# SCH___2022-10-18.net
KiCad netlist of a schematic drawn in EasyEDA
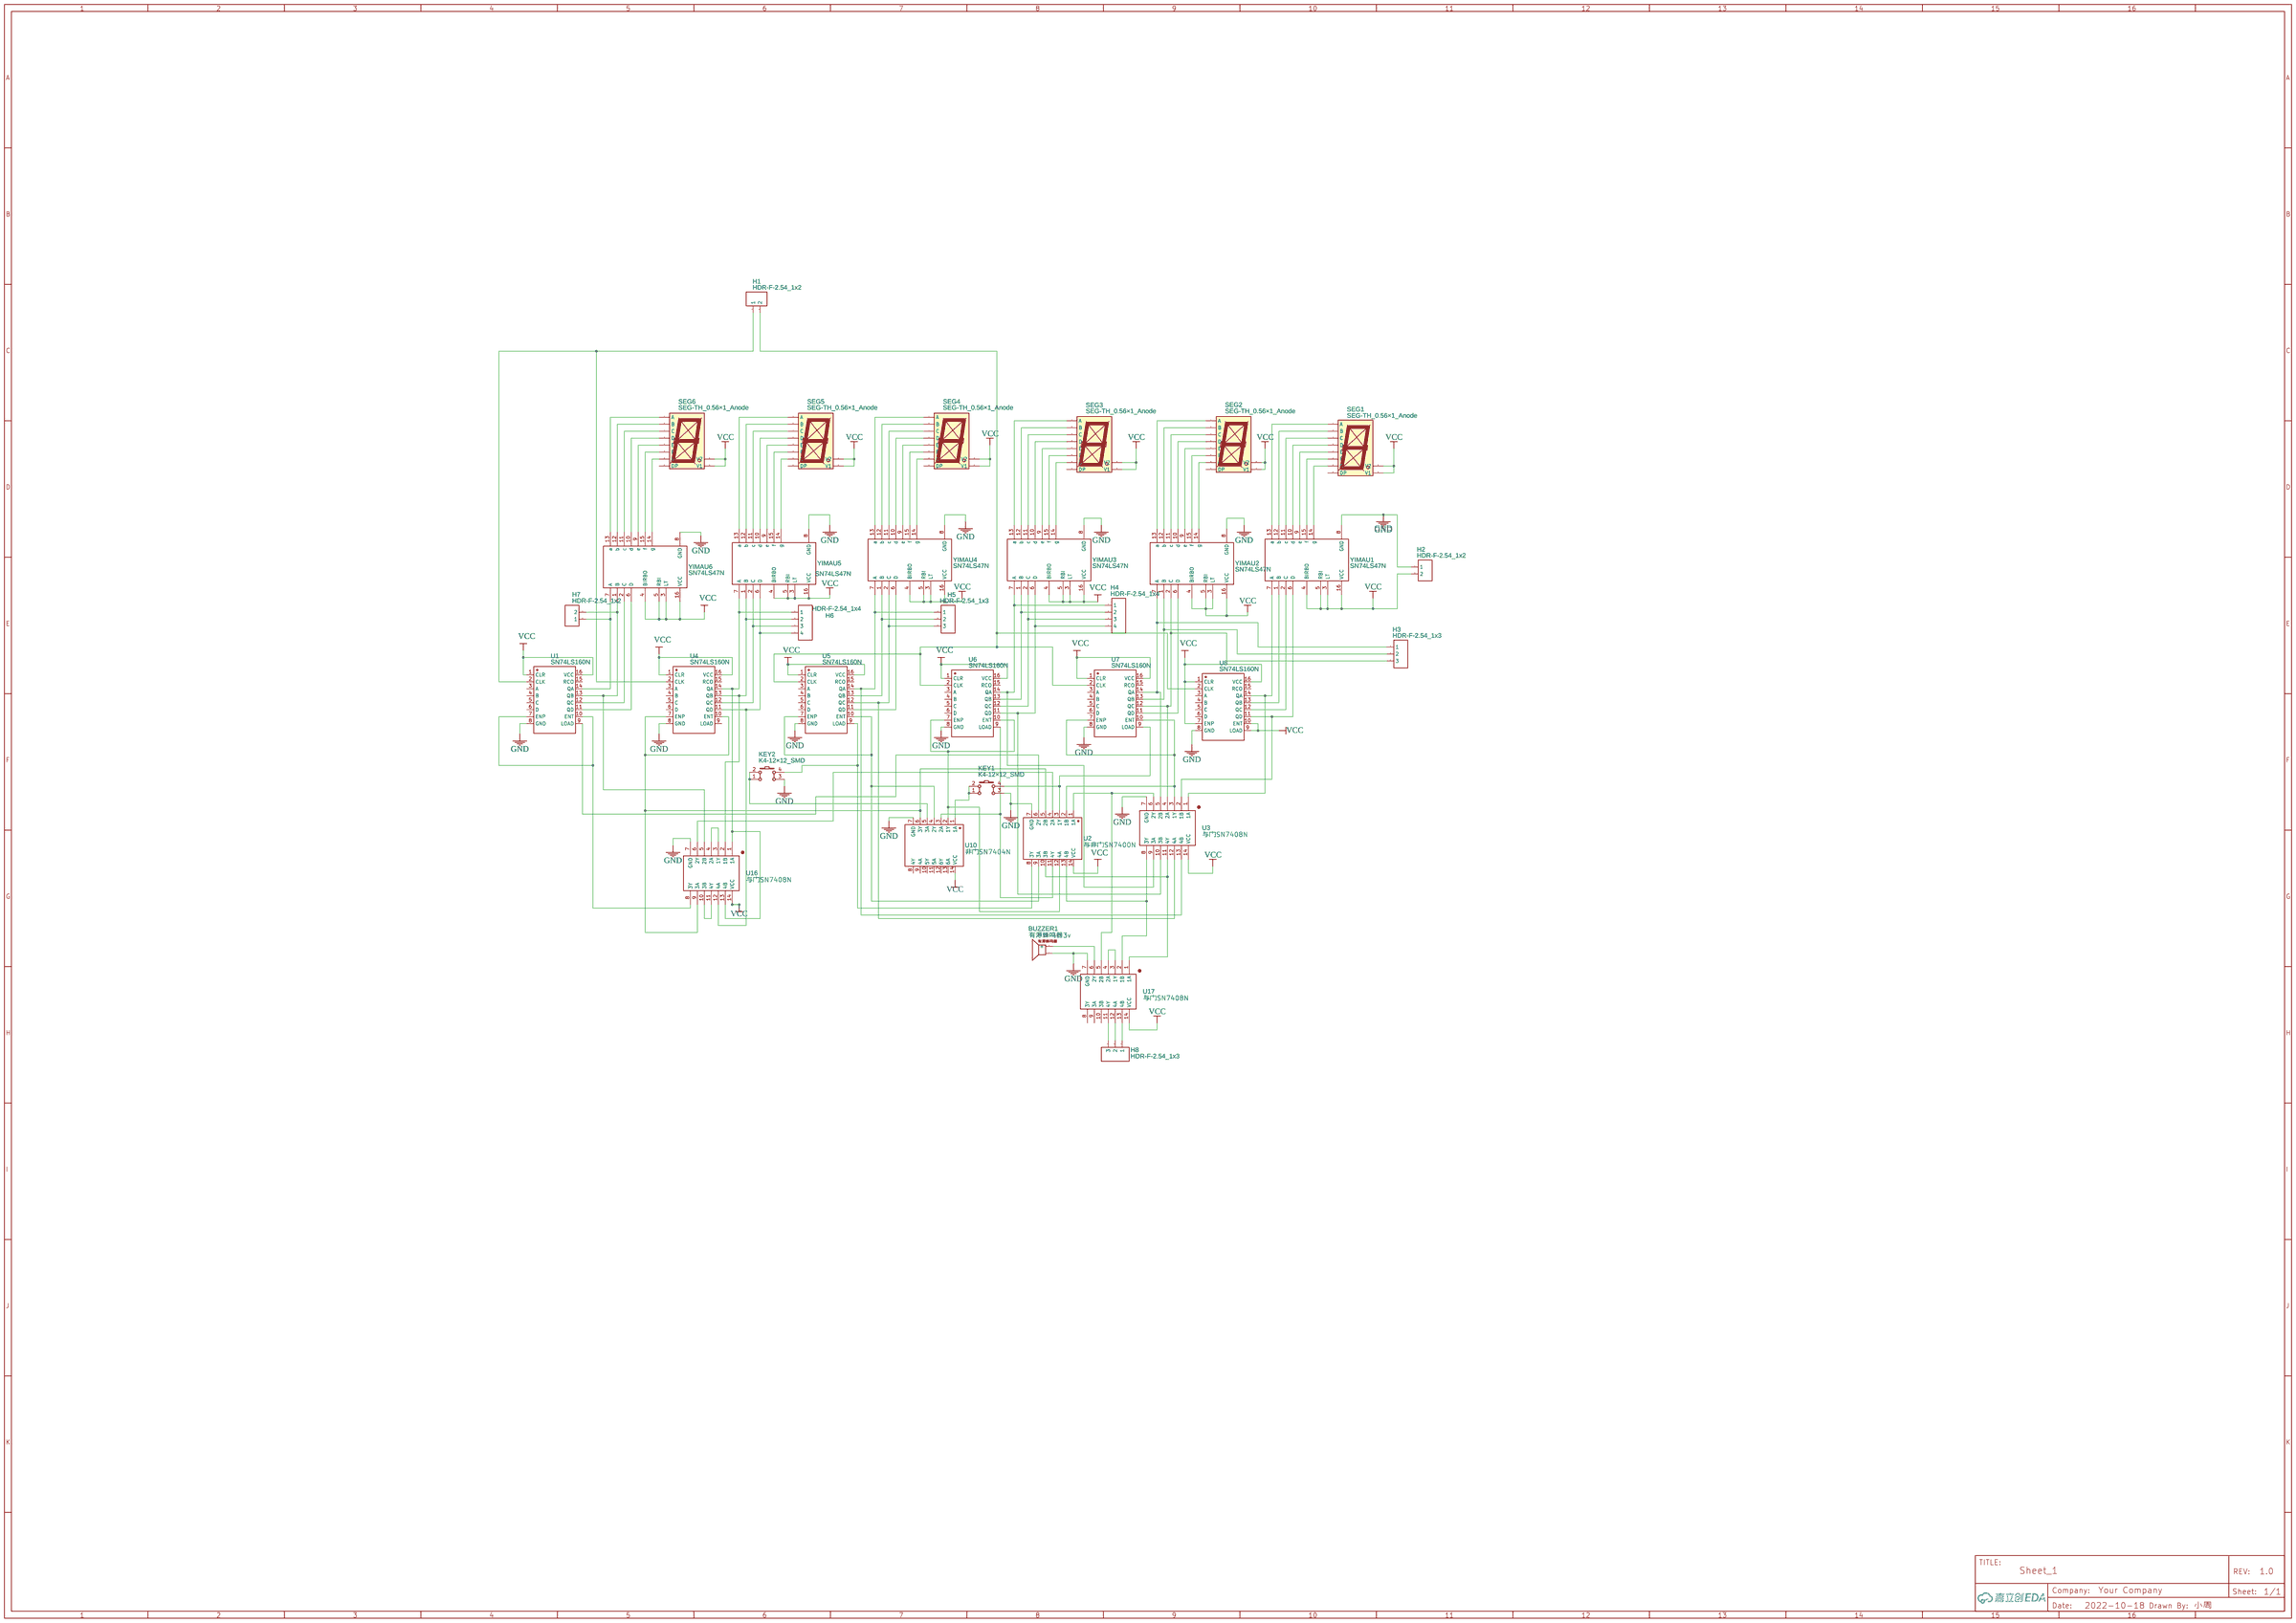
[diagram p0: schematic sheet]

(export (version "E")
  (design (tool "Eeschema 10.0.6"))
  (components
    (comp (ref "BUZZER1")
      (value "有源蜂鸣器3v")
      (fields (field (name "BOM_Manufacturer Part") "TMB12A12") (field (name "BOM_Supplier Part") "C96079"))
      (libsource (lib "") (part "有源蜂鸣器3v"))
    )
    (comp (ref "H1")
      (value "HDR-F-2.54_1x2")
      (fields (field (name "BOM_Supplier Part") "C49661"))
      (libsource (lib "") (part "HDR-F-2.54_1x2"))
    )
    (comp (ref "H2")
      (value "HDR-F-2.54_1x2")
      (fields (field (name "BOM_Supplier Part") "C49661"))
      (libsource (lib "") (part "HDR-F-2.54_1x2_2"))
    )
    (comp (ref "H3")
      (value "HDR-F-2.54_1x3")
      (fields (field (name "BOM_Supplier Part") "C146690"))
      (libsource (lib "") (part "HDR-F-2.54_1x3"))
    )
    (comp (ref "H4")
      (value "HDR-F-2.54_1x4")
      (fields (field (name "BOM_Supplier Part") "C225501"))
      (libsource (lib "") (part "HDR-F-2.54_1x4"))
    )
    (comp (ref "H5")
      (value "HDR-F-2.54_1x3")
      (fields (field (name "BOM_Supplier Part") "C146690"))
      (libsource (lib "") (part "HDR-F-2.54_1x3"))
    )
    (comp (ref "H6")
      (value "HDR-F-2.54_1x4")
      (fields (field (name "BOM_Supplier Part") "C225501"))
      (libsource (lib "") (part "HDR-F-2.54_1x4"))
    )
    (comp (ref "H7")
      (value "HDR-F-2.54_1x2")
      (fields (field (name "BOM_Supplier Part") "C49661"))
      (libsource (lib "") (part "HDR-F-2.54_1x2_1"))
    )
    (comp (ref "H8")
      (value "HDR-F-2.54_1x3")
      (fields (field (name "BOM_Supplier Part") "C146690"))
      (libsource (lib "") (part "HDR-F-2.54_1x3_1"))
    )
    (comp (ref "KEY1")
      (value "K4-12×12_SMD")
      (fields
        (field (name "BOM_Manufacturer Part") "K2-1103SP-E4SW-04")
        (field (name "BOM_Supplier Part") "C136697")
      )
      (libsource (lib "") (part "K4-12×12_SMD"))
    )
    (comp (ref "KEY2")
      (value "K4-12×12_SMD")
      (fields
        (field (name "BOM_Manufacturer Part") "K2-1103SP-E4SW-04")
        (field (name "BOM_Supplier Part") "C136697")
      )
      (libsource (lib "") (part "K4-12×12_SMD"))
    )
    (comp (ref "SEG1")
      (value "SEG-TH_0.56×1_Anode")
      (fields (field (name "BOM_Supplier Part") "C8092"))
      (libsource (lib "") (part "SEG-TH_0.56×1_Anode"))
    )
    (comp (ref "SEG2")
      (value "SEG-TH_0.56×1_Anode")
      (fields (field (name "BOM_Supplier Part") "C8092"))
      (libsource (lib "") (part "SEG-TH_0.56×1_Anode"))
    )
    (comp (ref "SEG3")
      (value "SEG-TH_0.56×1_Anode")
      (fields (field (name "BOM_Supplier Part") "C8092"))
      (libsource (lib "") (part "SEG-TH_0.56×1_Anode"))
    )
    (comp (ref "SEG4")
      (value "SEG-TH_0.56×1_Anode")
      (fields (field (name "BOM_Supplier Part") "C8092"))
      (libsource (lib "") (part "SEG-TH_0.56×1_Anode"))
    )
    (comp (ref "SEG5")
      (value "SEG-TH_0.56×1_Anode")
      (fields (field (name "BOM_Supplier Part") "C8092"))
      (libsource (lib "") (part "SEG-TH_0.56×1_Anode"))
    )
    (comp (ref "SEG6")
      (value "SEG-TH_0.56×1_Anode")
      (fields (field (name "BOM_Supplier Part") "C8092"))
      (libsource (lib "") (part "SEG-TH_0.56×1_Anode"))
    )
    (comp (ref "U1")
      (value "SN74LS160N")
      (fields
        (field (name "BOM_Manufacturer Part") "CC0805JRNPO9BN821")
        (field (name "BOM_Supplier Part") "C113834")
      )
      (libsource (lib "") (part "SN74LS160N"))
    )
    (comp (ref "U2") (value "与非门SN7400N") (libsource (lib "") (part "SN7400N")))
    (comp (ref "U3") (value "与门SN7408N") (libsource (lib "") (part "SN7408N")))
    (comp (ref "U4")
      (value "SN74LS160N")
      (fields
        (field (name "BOM_Manufacturer Part") "CC0805JRNPO9BN821")
        (field (name "BOM_Supplier Part") "C113834")
      )
      (libsource (lib "") (part "SN74LS160N"))
    )
    (comp (ref "U5")
      (value "SN74LS160N")
      (fields
        (field (name "BOM_Manufacturer Part") "CC0805JRNPO9BN821")
        (field (name "BOM_Supplier Part") "C113834")
      )
      (libsource (lib "") (part "SN74LS160N"))
    )
    (comp (ref "U6")
      (value "SN74LS160N")
      (fields
        (field (name "BOM_Manufacturer Part") "CC0805JRNPO9BN821")
        (field (name "BOM_Supplier Part") "C113834")
      )
      (libsource (lib "") (part "SN74LS160N"))
    )
    (comp (ref "U7")
      (value "SN74LS160N")
      (fields
        (field (name "BOM_Manufacturer Part") "CC0805JRNPO9BN821")
        (field (name "BOM_Supplier Part") "C113834")
      )
      (libsource (lib "") (part "SN74LS160N"))
    )
    (comp (ref "U8")
      (value "SN74LS160N")
      (fields
        (field (name "BOM_Manufacturer Part") "CC0805JRNPO9BN821")
        (field (name "BOM_Supplier Part") "C113834")
      )
      (libsource (lib "") (part "SN74LS160N"))
    )
    (comp (ref "U10") (value "非门SN7404N") (libsource (lib "") (part "SN7404N")))
    (comp (ref "U16") (value "与门SN7408N") (libsource (lib "") (part "SN7408N")))
    (comp (ref "U17") (value "与门SN7408N") (libsource (lib "") (part "SN7408N")))
    (comp (ref "YIMAU1")
      (value "SN74LS47N")
      (fields (field (name "BOM_Supplier Part") "C129379"))
      (libsource (lib "") (part "Unknown_1870_-1520"))
    )
    (comp (ref "YIMAU2")
      (value "SN74LS47N")
      (fields (field (name "BOM_Supplier Part") "C129379"))
      (libsource (lib "") (part "Unknown_1705_-1515"))
    )
    (comp (ref "YIMAU3")
      (value "SN74LS47N")
      (fields (field (name "BOM_Supplier Part") "C129379"))
      (libsource (lib "") (part "Unknown_1500_-1520"))
    )
    (comp (ref "YIMAU4")
      (value "SN74LS47N")
      (fields (field (name "BOM_Supplier Part") "C129379"))
      (libsource (lib "") (part "Unknown_1300_-1520"))
    )
    (comp (ref "YIMAU5")
      (value "SN74LS47N")
      (fields (field (name "BOM_Supplier Part") "C129379"))
      (libsource (lib "") (part "Unknown_1105_-1515"))
    )
    (comp (ref "YIMAU6")
      (value "SN74LS47N")
      (fields (field (name "BOM_Supplier Part") "C129379"))
      (libsource (lib "") (part "Unknown_920_-1510"))
    )
  )
  (nets
    (net (code "1") (name "GND") (class "Default")
      (node (ref "BUZZER1") (pin "-") (pinfunction "-_-") (pintype "unspecified"))
      (node (ref "H2") (pin "1") (pinfunction "1_1") (pintype "input"))
      (node (ref "KEY1") (pin "3") (pinfunction "3_3") (pintype "unspecified"))
      (node (ref "KEY2") (pin "3") (pinfunction "3_3") (pintype "unspecified"))
      (node (ref "U1") (pin "8") (pinfunction "GND_8") (pintype "unspecified"))
      (node (ref "U10") (pin "7") (pinfunction "GND_7") (pintype "unspecified"))
      (node (ref "U16") (pin "7") (pinfunction "GND_7") (pintype "unspecified"))
      (node (ref "U17") (pin "7") (pinfunction "GND_7") (pintype "unspecified"))
      (node (ref "U2") (pin "7") (pinfunction "GND_7") (pintype "unspecified"))
      (node (ref "U3") (pin "7") (pinfunction "GND_7") (pintype "unspecified"))
      (node (ref "U4") (pin "8") (pinfunction "GND_8") (pintype "unspecified"))
      (node (ref "U5") (pin "8") (pinfunction "GND_8") (pintype "unspecified"))
      (node (ref "U6") (pin "8") (pinfunction "GND_8") (pintype "unspecified"))
      (node (ref "U7") (pin "8") (pinfunction "GND_8") (pintype "unspecified"))
      (node (ref "U8") (pin "8") (pinfunction "GND_8") (pintype "unspecified"))
      (node (ref "YIMAU1") (pin "8") (pinfunction "GND_8") (pintype "passive"))
      (node (ref "YIMAU2") (pin "8") (pinfunction "GND_8") (pintype "passive"))
      (node (ref "YIMAU3") (pin "8") (pinfunction "GND_8") (pintype "passive"))
      (node (ref "YIMAU4") (pin "8") (pinfunction "GND_8") (pintype "passive"))
      (node (ref "YIMAU5") (pin "8") (pinfunction "GND_8") (pintype "passive"))
      (node (ref "YIMAU6") (pin "8") (pinfunction "GND_8") (pintype "passive"))
    )
    (net (code "2") (name "Net-(SEG1-A)") (class "Default")
      (node (ref "SEG1") (pin "7") (pinfunction "A_7") (pintype "unspecified"))
      (node (ref "YIMAU1") (pin "13") (pinfunction "a_13") (pintype "unspecified"))
    )
    (net (code "3") (name "Net-(SEG1-B)") (class "Default")
      (node (ref "SEG1") (pin "6") (pinfunction "B_6") (pintype "unspecified"))
      (node (ref "YIMAU1") (pin "12") (pinfunction "b_12") (pintype "unspecified"))
    )
    (net (code "4") (name "Net-(SEG1-C)") (class "Default")
      (node (ref "SEG1") (pin "4") (pinfunction "C_4") (pintype "unspecified"))
      (node (ref "YIMAU1") (pin "11") (pinfunction "c_11") (pintype "unspecified"))
    )
    (net (code "5") (name "Net-(SEG1-D)") (class "Default")
      (node (ref "SEG1") (pin "2") (pinfunction "D_2") (pintype "unspecified"))
      (node (ref "YIMAU1") (pin "10") (pinfunction "d_10") (pintype "unspecified"))
    )
    (net (code "6") (name "Net-(SEG1-E)") (class "Default")
      (node (ref "SEG1") (pin "1") (pinfunction "E_1") (pintype "unspecified"))
      (node (ref "YIMAU1") (pin "9") (pinfunction "e_9") (pintype "unspecified"))
    )
    (net (code "7") (name "Net-(SEG1-F)") (class "Default")
      (node (ref "SEG1") (pin "9") (pinfunction "F_9") (pintype "unspecified"))
      (node (ref "YIMAU1") (pin "15") (pinfunction "f_15") (pintype "unspecified"))
    )
    (net (code "8") (name "Net-(SEG1-G)") (class "Default")
      (node (ref "SEG1") (pin "10") (pinfunction "G_10") (pintype "unspecified"))
      (node (ref "YIMAU1") (pin "14") (pinfunction "g_14") (pintype "unspecified"))
    )
    (net (code "9") (name "Net-(SEG2-A)") (class "Default")
      (node (ref "SEG2") (pin "7") (pinfunction "A_7") (pintype "unspecified"))
      (node (ref "YIMAU2") (pin "13") (pinfunction "a_13") (pintype "unspecified"))
    )
    (net (code "10") (name "Net-(SEG2-B)") (class "Default")
      (node (ref "SEG2") (pin "6") (pinfunction "B_6") (pintype "unspecified"))
      (node (ref "YIMAU2") (pin "12") (pinfunction "b_12") (pintype "unspecified"))
    )
    (net (code "11") (name "Net-(SEG2-C)") (class "Default")
      (node (ref "SEG2") (pin "4") (pinfunction "C_4") (pintype "unspecified"))
      (node (ref "YIMAU2") (pin "11") (pinfunction "c_11") (pintype "unspecified"))
    )
    (net (code "12") (name "Net-(SEG2-D)") (class "Default")
      (node (ref "SEG2") (pin "2") (pinfunction "D_2") (pintype "unspecified"))
      (node (ref "YIMAU2") (pin "10") (pinfunction "d_10") (pintype "unspecified"))
    )
    (net (code "13") (name "Net-(SEG2-E)") (class "Default")
      (node (ref "SEG2") (pin "1") (pinfunction "E_1") (pintype "unspecified"))
      (node (ref "YIMAU2") (pin "9") (pinfunction "e_9") (pintype "unspecified"))
    )
    (net (code "14") (name "Net-(SEG2-F)") (class "Default")
      (node (ref "SEG2") (pin "9") (pinfunction "F_9") (pintype "unspecified"))
      (node (ref "YIMAU2") (pin "15") (pinfunction "f_15") (pintype "unspecified"))
    )
    (net (code "15") (name "Net-(SEG2-G)") (class "Default")
      (node (ref "SEG2") (pin "10") (pinfunction "G_10") (pintype "unspecified"))
      (node (ref "YIMAU2") (pin "14") (pinfunction "g_14") (pintype "unspecified"))
    )
    (net (code "16") (name "Net-(SEG3-A)") (class "Default")
      (node (ref "SEG3") (pin "7") (pinfunction "A_7") (pintype "unspecified"))
      (node (ref "YIMAU3") (pin "13") (pinfunction "a_13") (pintype "unspecified"))
    )
    (net (code "17") (name "Net-(SEG3-B)") (class "Default")
      (node (ref "SEG3") (pin "6") (pinfunction "B_6") (pintype "unspecified"))
      (node (ref "YIMAU3") (pin "12") (pinfunction "b_12") (pintype "unspecified"))
    )
    (net (code "18") (name "Net-(SEG3-C)") (class "Default")
      (node (ref "SEG3") (pin "4") (pinfunction "C_4") (pintype "unspecified"))
      (node (ref "YIMAU3") (pin "11") (pinfunction "c_11") (pintype "unspecified"))
    )
    (net (code "19") (name "Net-(SEG3-D)") (class "Default")
      (node (ref "SEG3") (pin "2") (pinfunction "D_2") (pintype "unspecified"))
      (node (ref "YIMAU3") (pin "10") (pinfunction "d_10") (pintype "unspecified"))
    )
    (net (code "20") (name "Net-(SEG3-E)") (class "Default")
      (node (ref "SEG3") (pin "1") (pinfunction "E_1") (pintype "unspecified"))
      (node (ref "YIMAU3") (pin "9") (pinfunction "e_9") (pintype "unspecified"))
    )
    (net (code "21") (name "Net-(SEG3-F)") (class "Default")
      (node (ref "SEG3") (pin "9") (pinfunction "F_9") (pintype "unspecified"))
      (node (ref "YIMAU3") (pin "15") (pinfunction "f_15") (pintype "unspecified"))
    )
    (net (code "22") (name "Net-(SEG3-G)") (class "Default")
      (node (ref "SEG3") (pin "10") (pinfunction "G_10") (pintype "unspecified"))
      (node (ref "YIMAU3") (pin "14") (pinfunction "g_14") (pintype "unspecified"))
    )
    (net (code "23") (name "Net-(SEG4-A)") (class "Default")
      (node (ref "SEG4") (pin "7") (pinfunction "A_7") (pintype "unspecified"))
      (node (ref "YIMAU4") (pin "13") (pinfunction "a_13") (pintype "unspecified"))
    )
    (net (code "24") (name "Net-(SEG4-B)") (class "Default")
      (node (ref "SEG4") (pin "6") (pinfunction "B_6") (pintype "unspecified"))
      (node (ref "YIMAU4") (pin "12") (pinfunction "b_12") (pintype "unspecified"))
    )
    (net (code "25") (name "Net-(SEG4-C)") (class "Default")
      (node (ref "SEG4") (pin "4") (pinfunction "C_4") (pintype "unspecified"))
      (node (ref "YIMAU4") (pin "11") (pinfunction "c_11") (pintype "unspecified"))
    )
    (net (code "26") (name "Net-(SEG4-D)") (class "Default")
      (node (ref "SEG4") (pin "2") (pinfunction "D_2") (pintype "unspecified"))
      (node (ref "YIMAU4") (pin "10") (pinfunction "d_10") (pintype "unspecified"))
    )
    (net (code "27") (name "Net-(SEG4-E)") (class "Default")
      (node (ref "SEG4") (pin "1") (pinfunction "E_1") (pintype "unspecified"))
      (node (ref "YIMAU4") (pin "9") (pinfunction "e_9") (pintype "unspecified"))
    )
    (net (code "28") (name "Net-(SEG4-F)") (class "Default")
      (node (ref "SEG4") (pin "9") (pinfunction "F_9") (pintype "unspecified"))
      (node (ref "YIMAU4") (pin "15") (pinfunction "f_15") (pintype "unspecified"))
    )
    (net (code "29") (name "Net-(SEG4-G)") (class "Default")
      (node (ref "SEG4") (pin "10") (pinfunction "G_10") (pintype "unspecified"))
      (node (ref "YIMAU4") (pin "14") (pinfunction "g_14") (pintype "unspecified"))
    )
    (net (code "30") (name "Net-(SEG5-A)") (class "Default")
      (node (ref "SEG5") (pin "7") (pinfunction "A_7") (pintype "unspecified"))
      (node (ref "YIMAU5") (pin "13") (pinfunction "a_13") (pintype "unspecified"))
    )
    (net (code "31") (name "Net-(SEG5-B)") (class "Default")
      (node (ref "SEG5") (pin "6") (pinfunction "B_6") (pintype "unspecified"))
      (node (ref "YIMAU5") (pin "12") (pinfunction "b_12") (pintype "unspecified"))
    )
    (net (code "32") (name "Net-(SEG5-C)") (class "Default")
      (node (ref "SEG5") (pin "4") (pinfunction "C_4") (pintype "unspecified"))
      (node (ref "YIMAU5") (pin "11") (pinfunction "c_11") (pintype "unspecified"))
    )
    (net (code "33") (name "Net-(SEG5-D)") (class "Default")
      (node (ref "SEG5") (pin "2") (pinfunction "D_2") (pintype "unspecified"))
      (node (ref "YIMAU5") (pin "10") (pinfunction "d_10") (pintype "unspecified"))
    )
    (net (code "34") (name "Net-(SEG5-E)") (class "Default")
      (node (ref "SEG5") (pin "1") (pinfunction "E_1") (pintype "unspecified"))
      (node (ref "YIMAU5") (pin "9") (pinfunction "e_9") (pintype "unspecified"))
    )
    (net (code "35") (name "Net-(SEG5-F)") (class "Default")
      (node (ref "SEG5") (pin "9") (pinfunction "F_9") (pintype "unspecified"))
      (node (ref "YIMAU5") (pin "15") (pinfunction "f_15") (pintype "unspecified"))
    )
    (net (code "36") (name "Net-(SEG5-G)") (class "Default")
      (node (ref "SEG5") (pin "10") (pinfunction "G_10") (pintype "unspecified"))
      (node (ref "YIMAU5") (pin "14") (pinfunction "g_14") (pintype "unspecified"))
    )
    (net (code "37") (name "Net-(SEG6-A)") (class "Default")
      (node (ref "SEG6") (pin "7") (pinfunction "A_7") (pintype "unspecified"))
      (node (ref "YIMAU6") (pin "13") (pinfunction "a_13") (pintype "unspecified"))
    )
    (net (code "38") (name "Net-(SEG6-B)") (class "Default")
      (node (ref "SEG6") (pin "6") (pinfunction "B_6") (pintype "unspecified"))
      (node (ref "YIMAU6") (pin "12") (pinfunction "b_12") (pintype "unspecified"))
    )
    (net (code "39") (name "Net-(SEG6-C)") (class "Default")
      (node (ref "SEG6") (pin "4") (pinfunction "C_4") (pintype "unspecified"))
      (node (ref "YIMAU6") (pin "11") (pinfunction "c_11") (pintype "unspecified"))
    )
    (net (code "40") (name "Net-(SEG6-D)") (class "Default")
      (node (ref "SEG6") (pin "2") (pinfunction "D_2") (pintype "unspecified"))
      (node (ref "YIMAU6") (pin "10") (pinfunction "d_10") (pintype "unspecified"))
    )
    (net (code "41") (name "Net-(SEG6-E)") (class "Default")
      (node (ref "SEG6") (pin "1") (pinfunction "E_1") (pintype "unspecified"))
      (node (ref "YIMAU6") (pin "9") (pinfunction "e_9") (pintype "unspecified"))
    )
    (net (code "42") (name "Net-(SEG6-F)") (class "Default")
      (node (ref "SEG6") (pin "9") (pinfunction "F_9") (pintype "unspecified"))
      (node (ref "YIMAU6") (pin "15") (pinfunction "f_15") (pintype "unspecified"))
    )
    (net (code "43") (name "Net-(SEG6-G)") (class "Default")
      (node (ref "SEG6") (pin "10") (pinfunction "G_10") (pintype "unspecified"))
      (node (ref "YIMAU6") (pin "14") (pinfunction "g_14") (pintype "unspecified"))
    )
    (net (code "44") (name "Net-(U1-CLK)") (class "Default")
      (node (ref "H1") (pin "1") (pinfunction "1_1") (pintype "input"))
      (node (ref "U1") (pin "2") (pinfunction "CLK_2") (pintype "unspecified"))
      (node (ref "U4") (pin "2") (pinfunction "CLK_2") (pintype "unspecified"))
    )
    (net (code "45") (name "Net-(U1-ENP)") (class "Default")
      (node (ref "U1") (pin "10") (pinfunction "ENT_10") (pintype "unspecified"))
      (node (ref "U1") (pin "7") (pinfunction "ENP_7") (pintype "unspecified"))
      (node (ref "U16") (pin "8") (pinfunction "3Y_8") (pintype "unspecified"))
    )
    (net (code "46") (name "Net-(U1-LOAD)") (class "Default")
      (node (ref "U1") (pin "9") (pinfunction "LOAD_9") (pintype "unspecified"))
      (node (ref "U2") (pin "6") (pinfunction "2Y_6") (pintype "unspecified"))
    )
    (net (code "47") (name "Net-(U1-QA)") (class "Default")
      (node (ref "H7") (pin "1") (pinfunction "1_1") (pintype "input"))
      (node (ref "U1") (pin "14") (pinfunction "QA_14") (pintype "unspecified"))
      (node (ref "YIMAU6") (pin "7") (pinfunction "A_7") (pintype "unspecified"))
    )
    (net (code "48") (name "Net-(U1-QB)") (class "Default")
      (node (ref "H7") (pin "2") (pinfunction "2_2") (pintype "input"))
      (node (ref "U1") (pin "13") (pinfunction "QB_13") (pintype "unspecified"))
      (node (ref "U16") (pin "5") (pinfunction "2B_5") (pintype "unspecified"))
      (node (ref "YIMAU6") (pin "1") (pinfunction "B_1") (pintype "unspecified"))
    )
    (net (code "49") (name "Net-(U1-QC)") (class "Default")
      (node (ref "U1") (pin "12") (pinfunction "QC_12") (pintype "unspecified"))
      (node (ref "YIMAU6") (pin "2") (pinfunction "C_2") (pintype "unspecified"))
    )
    (net (code "50") (name "Net-(U1-QD)") (class "Default")
      (node (ref "U1") (pin "11") (pinfunction "QD_11") (pintype "unspecified"))
      (node (ref "YIMAU6") (pin "6") (pinfunction "D_6") (pintype "unspecified"))
    )
    (net (code "51") (name "Net-(U2-1B)") (class "Default")
      (node (ref "U2") (pin "2") (pinfunction "1B_2") (pintype "unspecified"))
      (node (ref "U3") (pin "3") (pinfunction "1Y_3") (pintype "unspecified"))
      (node (ref "U7") (pin "10") (pinfunction "ENT_10") (pintype "unspecified"))
      (node (ref "U7") (pin "7") (pinfunction "ENP_7") (pintype "unspecified"))
    )
    (net (code "52") (name "Net-(U2-1Y)") (class "Default")
      (node (ref "KEY1") (pin "4") (pinfunction "4_4") (pintype "unspecified"))
      (node (ref "U2") (pin "3") (pinfunction "1Y_3") (pintype "unspecified"))
      (node (ref "U7") (pin "9") (pinfunction "LOAD_9") (pintype "unspecified"))
    )
    (net (code "53") (name "Net-(U2-3Y)") (class "Default")
      (node (ref "KEY2") (pin "4") (pinfunction "4_4") (pintype "unspecified"))
      (node (ref "U2") (pin "8") (pinfunction "3Y_8") (pintype "unspecified"))
      (node (ref "U5") (pin "9") (pinfunction "LOAD_9") (pintype "unspecified"))
    )
    (net (code "54") (name "Net-(U3-1A)") (class "Default")
      (node (ref "U3") (pin "1") (pinfunction "1A_1") (pintype "unspecified"))
      (node (ref "U8") (pin "14") (pinfunction "QA_14") (pintype "unspecified"))
      (node (ref "YIMAU1") (pin "7") (pinfunction "A_7") (pintype "unspecified"))
    )
    (net (code "55") (name "Net-(U3-1B)") (class "Default")
      (node (ref "U3") (pin "2") (pinfunction "1B_2") (pintype "unspecified"))
      (node (ref "U8") (pin "11") (pinfunction "QD_11") (pintype "unspecified"))
      (node (ref "YIMAU1") (pin "6") (pinfunction "D_6") (pintype "unspecified"))
    )
    (net (code "56") (name "Net-(U3-2A)") (class "Default")
      (node (ref "H3") (pin "3") (pinfunction "3_3") (pintype "input"))
      (node (ref "U3") (pin "4") (pinfunction "2A_4") (pintype "unspecified"))
      (node (ref "U7") (pin "12") (pinfunction "QC_12") (pintype "unspecified"))
      (node (ref "YIMAU2") (pin "2") (pinfunction "C_2") (pintype "unspecified"))
    )
    (net (code "57") (name "Net-(U3-2B)") (class "Default")
      (node (ref "H3") (pin "1") (pinfunction "1_1") (pintype "input"))
      (node (ref "U3") (pin "5") (pinfunction "2B_5") (pintype "unspecified"))
      (node (ref "U7") (pin "14") (pinfunction "QA_14") (pintype "unspecified"))
      (node (ref "YIMAU2") (pin "7") (pinfunction "A_7") (pintype "unspecified"))
    )
    (net (code "58") (name "Net-(U3-3A)") (class "Default")
      (node (ref "H4") (pin "1") (pinfunction "1_1") (pintype "unspecified"))
      (node (ref "U3") (pin "9") (pinfunction "3A_9") (pintype "unspecified"))
      (node (ref "U6") (pin "14") (pinfunction "QA_14") (pintype "unspecified"))
      (node (ref "YIMAU3") (pin "7") (pinfunction "A_7") (pintype "unspecified"))
    )
    (net (code "59") (name "Net-(U3-3B)") (class "Default")
      (node (ref "H4") (pin "4") (pinfunction "4_4") (pintype "unspecified"))
      (node (ref "U3") (pin "10") (pinfunction "3B_10") (pintype "unspecified"))
      (node (ref "U6") (pin "11") (pinfunction "QD_11") (pintype "unspecified"))
      (node (ref "YIMAU3") (pin "6") (pinfunction "D_6") (pintype "unspecified"))
    )
    (net (code "60") (name "Net-(U3-4A)") (class "Default")
      (node (ref "H5") (pin "3") (pinfunction "3_3") (pintype "input"))
      (node (ref "U3") (pin "12") (pinfunction "4A_12") (pintype "unspecified"))
      (node (ref "U5") (pin "12") (pinfunction "QC_12") (pintype "unspecified"))
      (node (ref "YIMAU4") (pin "2") (pinfunction "C_2") (pintype "unspecified"))
    )
    (net (code "61") (name "Net-(U3-4B)") (class "Default")
      (node (ref "H5") (pin "1") (pinfunction "1_1") (pintype "input"))
      (node (ref "U3") (pin "13") (pinfunction "4B_13") (pintype "unspecified"))
      (node (ref "U5") (pin "14") (pinfunction "QA_14") (pintype "unspecified"))
      (node (ref "YIMAU4") (pin "7") (pinfunction "A_7") (pintype "unspecified"))
    )
    (net (code "62") (name "Net-(U4-QC)") (class "Default")
      (node (ref "H6") (pin "3") (pinfunction "3_3") (pintype "unspecified"))
      (node (ref "U4") (pin "12") (pinfunction "QC_12") (pintype "unspecified"))
      (node (ref "YIMAU5") (pin "2") (pinfunction "C_2") (pintype "unspecified"))
    )
    (net (code "63") (name "Net-(U5-CLK)") (class "Default")
      (node (ref "H1") (pin "2") (pinfunction "2_2") (pintype "input"))
      (node (ref "U5") (pin "2") (pinfunction "CLK_2") (pintype "unspecified"))
      (node (ref "U6") (pin "2") (pinfunction "CLK_2") (pintype "unspecified"))
      (node (ref "U7") (pin "2") (pinfunction "CLK_2") (pintype "unspecified"))
      (node (ref "U8") (pin "2") (pinfunction "CLK_2") (pintype "unspecified"))
    )
    (net (code "64") (name "Net-(U5-QB)") (class "Default")
      (node (ref "H5") (pin "2") (pinfunction "2_2") (pintype "input"))
      (node (ref "U5") (pin "13") (pinfunction "QB_13") (pintype "unspecified"))
      (node (ref "YIMAU4") (pin "1") (pinfunction "B_1") (pintype "unspecified"))
    )
    (net (code "65") (name "Net-(U5-QD)") (class "Default")
      (node (ref "U5") (pin "11") (pinfunction "QD_11") (pintype "unspecified"))
      (node (ref "YIMAU4") (pin "6") (pinfunction "D_6") (pintype "unspecified"))
    )
    (net (code "66") (name "Net-(U6-QB)") (class "Default")
      (node (ref "H4") (pin "2") (pinfunction "2_2") (pintype "unspecified"))
      (node (ref "U6") (pin "13") (pinfunction "QB_13") (pintype "unspecified"))
      (node (ref "YIMAU3") (pin "1") (pinfunction "B_1") (pintype "unspecified"))
    )
    (net (code "67") (name "Net-(U6-QC)") (class "Default")
      (node (ref "H4") (pin "3") (pinfunction "3_3") (pintype "unspecified"))
      (node (ref "U6") (pin "12") (pinfunction "QC_12") (pintype "unspecified"))
      (node (ref "YIMAU3") (pin "2") (pinfunction "C_2") (pintype "unspecified"))
    )
    (net (code "68") (name "Net-(U7-QB)") (class "Default")
      (node (ref "H3") (pin "2") (pinfunction "2_2") (pintype "input"))
      (node (ref "U7") (pin "13") (pinfunction "QB_13") (pintype "unspecified"))
      (node (ref "YIMAU2") (pin "1") (pinfunction "B_1") (pintype "unspecified"))
    )
    (net (code "69") (name "Net-(U7-QD)") (class "Default")
      (node (ref "U7") (pin "11") (pinfunction "QD_11") (pintype "unspecified"))
      (node (ref "YIMAU2") (pin "6") (pinfunction "D_6") (pintype "unspecified"))
    )
    (net (code "70") (name "Net-(U8-QB)") (class "Default")
      (node (ref "U8") (pin "13") (pinfunction "QB_13") (pintype "unspecified"))
      (node (ref "YIMAU1") (pin "1") (pinfunction "B_1") (pintype "unspecified"))
    )
    (net (code "71") (name "Net-(U8-QC)") (class "Default")
      (node (ref "U8") (pin "12") (pinfunction "QC_12") (pintype "unspecified"))
      (node (ref "YIMAU1") (pin "2") (pinfunction "C_2") (pintype "unspecified"))
    )
    (net (code "72") (name "Net-(U10-1A)") (class "Default")
      (node (ref "KEY1") (pin "1") (pinfunction "1_1") (pintype "unspecified"))
      (node (ref "KEY1") (pin "2") (pinfunction "2_2") (pintype "unspecified"))
      (node (ref "U10") (pin "1") (pinfunction "1A_1") (pintype "unspecified"))
    )
    (net (code "73") (name "Net-(U10-1Y)") (class "Default")
      (node (ref "U10") (pin "2") (pinfunction "1Y_2") (pintype "unspecified"))
      (node (ref "U2") (pin "12") (pinfunction "4A_12") (pintype "unspecified"))
      (node (ref "U6") (pin "10") (pinfunction "ENT_10") (pintype "unspecified"))
      (node (ref "U6") (pin "7") (pinfunction "ENP_7") (pintype "unspecified"))
    )
    (net (code "74") (name "Net-(U10-2A)") (class "Default")
      (node (ref "U10") (pin "3") (pinfunction "2A_3") (pintype "unspecified"))
      (node (ref "U2") (pin "11") (pinfunction "4Y_11") (pintype "unspecified"))
      (node (ref "U6") (pin "9") (pinfunction "LOAD_9") (pintype "unspecified"))
    )
    (net (code "75") (name "Net-(U10-2Y)") (class "Default")
      (node (ref "U10") (pin "4") (pinfunction "2Y_4") (pintype "unspecified"))
      (node (ref "U2") (pin "9") (pinfunction "3A_9") (pintype "unspecified"))
      (node (ref "U5") (pin "10") (pinfunction "ENT_10") (pintype "unspecified"))
      (node (ref "U5") (pin "7") (pinfunction "ENP_7") (pintype "unspecified"))
    )
    (net (code "76") (name "Net-(U10-3A)") (class "Default")
      (node (ref "KEY2") (pin "1") (pinfunction "1_1") (pintype "unspecified"))
      (node (ref "KEY2") (pin "2") (pinfunction "2_2") (pintype "unspecified"))
      (node (ref "U10") (pin "5") (pinfunction "3A_5") (pintype "unspecified"))
    )
    (net (code "77") (name "Net-(U10-3Y)") (class "Default")
      (node (ref "U10") (pin "6") (pinfunction "3Y_6") (pintype "unspecified"))
      (node (ref "U16") (pin "9") (pinfunction "3A_9") (pintype "unspecified"))
      (node (ref "U2") (pin "5") (pinfunction "2B_5") (pintype "unspecified"))
      (node (ref "U4") (pin "10") (pinfunction "ENT_10") (pintype "unspecified"))
      (node (ref "U4") (pin "7") (pinfunction "ENP_7") (pintype "unspecified"))
    )
    (net (code "78") (name "Net-(U16-1A)") (class "Default")
      (node (ref "H6") (pin "1") (pinfunction "1_1") (pintype "unspecified"))
      (node (ref "U16") (pin "1") (pinfunction "1A_1") (pintype "unspecified"))
      (node (ref "U16") (pin "13") (pinfunction "4B_13") (pintype "unspecified"))
      (node (ref "U4") (pin "14") (pinfunction "QA_14") (pintype "unspecified"))
      (node (ref "YIMAU5") (pin "7") (pinfunction "A_7") (pintype "unspecified"))
    )
    (net (code "79") (name "Net-(U16-1B)") (class "Default")
      (node (ref "H6") (pin "2") (pinfunction "2_2") (pintype "unspecified"))
      (node (ref "U16") (pin "2") (pinfunction "1B_2") (pintype "unspecified"))
      (node (ref "U4") (pin "13") (pinfunction "QB_13") (pintype "unspecified"))
      (node (ref "YIMAU5") (pin "1") (pinfunction "B_1") (pintype "unspecified"))
    )
    (net (code "80") (name "Net-(U16-1Y)") (class "Default")
      (node (ref "U16") (pin "3") (pinfunction "1Y_3") (pintype "unspecified"))
      (node (ref "U16") (pin "4") (pinfunction "2A_4") (pintype "unspecified"))
    )
    (net (code "81") (name "Net-(U16-2Y)") (class "Default")
      (node (ref "U16") (pin "6") (pinfunction "2Y_6") (pintype "unspecified"))
      (node (ref "U2") (pin "4") (pinfunction "2A_4") (pintype "unspecified"))
    )
    (net (code "82") (name "Net-(U16-3B)") (class "Default")
      (node (ref "U16") (pin "10") (pinfunction "3B_10") (pintype "unspecified"))
      (node (ref "U16") (pin "11") (pinfunction "4Y_11") (pintype "unspecified"))
    )
    (net (code "83") (name "Net-(U16-4A)") (class "Default")
      (node (ref "H6") (pin "4") (pinfunction "4_4") (pintype "unspecified"))
      (node (ref "U16") (pin "12") (pinfunction "4A_12") (pintype "unspecified"))
      (node (ref "U4") (pin "11") (pinfunction "QD_11") (pintype "unspecified"))
      (node (ref "YIMAU5") (pin "6") (pinfunction "D_6") (pintype "unspecified"))
    )
    (net (code "84") (name "Net-(U17-1A)") (class "Default")
      (node (ref "U17") (pin "1") (pinfunction "1A_1") (pintype "unspecified"))
      (node (ref "U2") (pin "10") (pinfunction "3B_10") (pintype "unspecified"))
      (node (ref "U3") (pin "11") (pinfunction "4Y_11") (pintype "unspecified"))
    )
    (net (code "85") (name "Net-(U17-1B)") (class "Default")
      (node (ref "U17") (pin "2") (pinfunction "1B_2") (pintype "unspecified"))
      (node (ref "U2") (pin "13") (pinfunction "4B_13") (pintype "unspecified"))
      (node (ref "U3") (pin "8") (pinfunction "3Y_8") (pintype "unspecified"))
    )
    (net (code "86") (name "Net-(U17-1Y)") (class "Default")
      (node (ref "U17") (pin "3") (pinfunction "1Y_3") (pintype "unspecified"))
      (node (ref "U17") (pin "4") (pinfunction "2A_4") (pintype "unspecified"))
    )
    (net (code "87") (name "Net-(U17-2B)") (class "Default")
      (node (ref "U17") (pin "5") (pinfunction "2B_5") (pintype "unspecified"))
      (node (ref "U2") (pin "1") (pinfunction "1A_1") (pintype "unspecified"))
      (node (ref "U3") (pin "6") (pinfunction "2Y_6") (pintype "unspecified"))
    )
    (net (code "88") (name "Net-(U17-2Y)") (class "Default")
      (node (ref "BUZZER1") (pin "+") (pinfunction "+_+") (pintype "unspecified"))
      (node (ref "U17") (pin "6") (pinfunction "2Y_6") (pintype "unspecified"))
    )
    (net (code "89") (name "Net-(U17-4A)") (class "Default")
      (node (ref "H8") (pin "2") (pinfunction "2_2") (pintype "input"))
      (node (ref "U17") (pin "12") (pinfunction "4A_12") (pintype "unspecified"))
    )
    (net (code "90") (name "Net-(U17-4B)") (class "Default")
      (node (ref "H8") (pin "1") (pinfunction "1_1") (pintype "input"))
      (node (ref "U17") (pin "13") (pinfunction "4B_13") (pintype "unspecified"))
    )
    (net (code "91") (name "Net-(U17-4Y)") (class "Default")
      (node (ref "H8") (pin "3") (pinfunction "3_3") (pintype "input"))
      (node (ref "U17") (pin "11") (pinfunction "4Y_11") (pintype "unspecified"))
    )
    (net (code "92") (name "VCC") (class "Default")
      (node (ref "H2") (pin "2") (pinfunction "2_2") (pintype "input"))
      (node (ref "SEG1") (pin "3") (pinfunction "V1_3") (pintype "unspecified"))
      (node (ref "SEG1") (pin "8") (pinfunction "V2_8") (pintype "unspecified"))
      (node (ref "SEG2") (pin "3") (pinfunction "V1_3") (pintype "unspecified"))
      (node (ref "SEG2") (pin "8") (pinfunction "V2_8") (pintype "unspecified"))
      (node (ref "SEG3") (pin "3") (pinfunction "V1_3") (pintype "unspecified"))
      (node (ref "SEG3") (pin "8") (pinfunction "V2_8") (pintype "unspecified"))
      (node (ref "SEG4") (pin "3") (pinfunction "V1_3") (pintype "unspecified"))
      (node (ref "SEG4") (pin "8") (pinfunction "V2_8") (pintype "unspecified"))
      (node (ref "SEG5") (pin "3") (pinfunction "V1_3") (pintype "unspecified"))
      (node (ref "SEG5") (pin "8") (pinfunction "V2_8") (pintype "unspecified"))
      (node (ref "SEG6") (pin "3") (pinfunction "V1_3") (pintype "unspecified"))
      (node (ref "SEG6") (pin "8") (pinfunction "V2_8") (pintype "unspecified"))
      (node (ref "U1") (pin "1") (pinfunction "CLR_1") (pintype "unspecified"))
      (node (ref "U1") (pin "16") (pinfunction "VCC_16") (pintype "unspecified"))
      (node (ref "U10") (pin "14") (pinfunction "VCC_14") (pintype "unspecified"))
      (node (ref "U16") (pin "14") (pinfunction "VCC_14") (pintype "unspecified"))
      (node (ref "U17") (pin "14") (pinfunction "VCC_14") (pintype "unspecified"))
      (node (ref "U2") (pin "14") (pinfunction "VCC_14") (pintype "unspecified"))
      (node (ref "U3") (pin "14") (pinfunction "VCC_14") (pintype "unspecified"))
      (node (ref "U4") (pin "1") (pinfunction "CLR_1") (pintype "unspecified"))
      (node (ref "U4") (pin "16") (pinfunction "VCC_16") (pintype "unspecified"))
      (node (ref "U5") (pin "1") (pinfunction "CLR_1") (pintype "unspecified"))
      (node (ref "U5") (pin "16") (pinfunction "VCC_16") (pintype "unspecified"))
      (node (ref "U6") (pin "1") (pinfunction "CLR_1") (pintype "unspecified"))
      (node (ref "U6") (pin "16") (pinfunction "VCC_16") (pintype "unspecified"))
      (node (ref "U7") (pin "1") (pinfunction "CLR_1") (pintype "unspecified"))
      (node (ref "U7") (pin "16") (pinfunction "VCC_16") (pintype "unspecified"))
      (node (ref "U8") (pin "1") (pinfunction "CLR_1") (pintype "unspecified"))
      (node (ref "U8") (pin "10") (pinfunction "ENT_10") (pintype "unspecified"))
      (node (ref "U8") (pin "16") (pinfunction "VCC_16") (pintype "unspecified"))
      (node (ref "U8") (pin "7") (pinfunction "ENP_7") (pintype "unspecified"))
      (node (ref "U8") (pin "9") (pinfunction "LOAD_9") (pintype "unspecified"))
      (node (ref "YIMAU1") (pin "16") (pinfunction "VCC_16") (pintype "passive"))
      (node (ref "YIMAU1") (pin "3") (pinfunction "LT_3") (pintype "unspecified"))
      (node (ref "YIMAU1") (pin "4") (pinfunction "BIRBO_4") (pintype "bidirectional"))
      (node (ref "YIMAU1") (pin "5") (pinfunction "RBI_5") (pintype "unspecified"))
      (node (ref "YIMAU2") (pin "16") (pinfunction "VCC_16") (pintype "passive"))
      (node (ref "YIMAU2") (pin "3") (pinfunction "LT_3") (pintype "unspecified"))
      (node (ref "YIMAU2") (pin "4") (pinfunction "BIRBO_4") (pintype "bidirectional"))
      (node (ref "YIMAU2") (pin "5") (pinfunction "RBI_5") (pintype "unspecified"))
      (node (ref "YIMAU3") (pin "16") (pinfunction "VCC_16") (pintype "passive"))
      (node (ref "YIMAU3") (pin "3") (pinfunction "LT_3") (pintype "unspecified"))
      (node (ref "YIMAU3") (pin "4") (pinfunction "BIRBO_4") (pintype "bidirectional"))
      (node (ref "YIMAU3") (pin "5") (pinfunction "RBI_5") (pintype "unspecified"))
      (node (ref "YIMAU4") (pin "16") (pinfunction "VCC_16") (pintype "passive"))
      (node (ref "YIMAU4") (pin "3") (pinfunction "LT_3") (pintype "unspecified"))
      (node (ref "YIMAU4") (pin "4") (pinfunction "BIRBO_4") (pintype "bidirectional"))
      (node (ref "YIMAU4") (pin "5") (pinfunction "RBI_5") (pintype "unspecified"))
      (node (ref "YIMAU5") (pin "16") (pinfunction "VCC_16") (pintype "passive"))
      (node (ref "YIMAU5") (pin "3") (pinfunction "LT_3") (pintype "unspecified"))
      (node (ref "YIMAU5") (pin "4") (pinfunction "BIRBO_4") (pintype "bidirectional"))
      (node (ref "YIMAU5") (pin "5") (pinfunction "RBI_5") (pintype "unspecified"))
      (node (ref "YIMAU6") (pin "16") (pinfunction "VCC_16") (pintype "passive"))
      (node (ref "YIMAU6") (pin "3") (pinfunction "LT_3") (pintype "unspecified"))
      (node (ref "YIMAU6") (pin "4") (pinfunction "BIRBO_4") (pintype "bidirectional"))
      (node (ref "YIMAU6") (pin "5") (pinfunction "RBI_5") (pintype "unspecified"))
    )
    (net (code "93") (name "unconnected-(SEG1-DP-Pad5)") (class "Default")
      (node (ref "SEG1") (pin "5") (pinfunction "DP_5") (pintype "unspecified"))
    )
    (net (code "94") (name "unconnected-(SEG2-DP-Pad5)") (class "Default")
      (node (ref "SEG2") (pin "5") (pinfunction "DP_5") (pintype "unspecified"))
    )
    (net (code "95") (name "unconnected-(SEG3-DP-Pad5)") (class "Default")
      (node (ref "SEG3") (pin "5") (pinfunction "DP_5") (pintype "unspecified"))
    )
    (net (code "96") (name "unconnected-(SEG4-DP-Pad5)") (class "Default")
      (node (ref "SEG4") (pin "5") (pinfunction "DP_5") (pintype "unspecified"))
    )
    (net (code "97") (name "unconnected-(SEG5-DP-Pad5)") (class "Default")
      (node (ref "SEG5") (pin "5") (pinfunction "DP_5") (pintype "unspecified"))
    )
    (net (code "98") (name "unconnected-(SEG6-DP-Pad5)") (class "Default")
      (node (ref "SEG6") (pin "5") (pinfunction "DP_5") (pintype "unspecified"))
    )
    (net (code "99") (name "unconnected-(U1-A-Pad3)") (class "Default")
      (node (ref "U1") (pin "3") (pinfunction "A_3") (pintype "unspecified"))
    )
    (net (code "100") (name "unconnected-(U1-B-Pad4)") (class "Default")
      (node (ref "U1") (pin "4") (pinfunction "B_4") (pintype "unspecified"))
    )
    (net (code "101") (name "unconnected-(U1-C-Pad5)") (class "Default")
      (node (ref "U1") (pin "5") (pinfunction "C_5") (pintype "unspecified"))
    )
    (net (code "102") (name "unconnected-(U1-D-Pad6)") (class "Default")
      (node (ref "U1") (pin "6") (pinfunction "D_6") (pintype "unspecified"))
    )
    (net (code "103") (name "unconnected-(U1-RCO-Pad15)") (class "Default")
      (node (ref "U1") (pin "15") (pinfunction "RCO_15") (pintype "unspecified"))
    )
    (net (code "104") (name "unconnected-(U4-A-Pad3)") (class "Default")
      (node (ref "U4") (pin "3") (pinfunction "A_3") (pintype "unspecified"))
    )
    (net (code "105") (name "unconnected-(U4-B-Pad4)") (class "Default")
      (node (ref "U4") (pin "4") (pinfunction "B_4") (pintype "unspecified"))
    )
    (net (code "106") (name "unconnected-(U4-C-Pad5)") (class "Default")
      (node (ref "U4") (pin "5") (pinfunction "C_5") (pintype "unspecified"))
    )
    (net (code "107") (name "unconnected-(U4-D-Pad6)") (class "Default")
      (node (ref "U4") (pin "6") (pinfunction "D_6") (pintype "unspecified"))
    )
    (net (code "108") (name "unconnected-(U4-LOAD-Pad9)") (class "Default")
      (node (ref "U4") (pin "9") (pinfunction "LOAD_9") (pintype "unspecified"))
    )
    (net (code "109") (name "unconnected-(U4-RCO-Pad15)") (class "Default")
      (node (ref "U4") (pin "15") (pinfunction "RCO_15") (pintype "unspecified"))
    )
    (net (code "110") (name "unconnected-(U5-A-Pad3)") (class "Default")
      (node (ref "U5") (pin "3") (pinfunction "A_3") (pintype "unspecified"))
    )
    (net (code "111") (name "unconnected-(U5-B-Pad4)") (class "Default")
      (node (ref "U5") (pin "4") (pinfunction "B_4") (pintype "unspecified"))
    )
    (net (code "112") (name "unconnected-(U5-C-Pad5)") (class "Default")
      (node (ref "U5") (pin "5") (pinfunction "C_5") (pintype "unspecified"))
    )
    (net (code "113") (name "unconnected-(U5-D-Pad6)") (class "Default")
      (node (ref "U5") (pin "6") (pinfunction "D_6") (pintype "unspecified"))
    )
    (net (code "114") (name "unconnected-(U5-RCO-Pad15)") (class "Default")
      (node (ref "U5") (pin "15") (pinfunction "RCO_15") (pintype "unspecified"))
    )
    (net (code "115") (name "unconnected-(U6-A-Pad3)") (class "Default")
      (node (ref "U6") (pin "3") (pinfunction "A_3") (pintype "unspecified"))
    )
    (net (code "116") (name "unconnected-(U6-B-Pad4)") (class "Default")
      (node (ref "U6") (pin "4") (pinfunction "B_4") (pintype "unspecified"))
    )
    (net (code "117") (name "unconnected-(U6-C-Pad5)") (class "Default")
      (node (ref "U6") (pin "5") (pinfunction "C_5") (pintype "unspecified"))
    )
    (net (code "118") (name "unconnected-(U6-D-Pad6)") (class "Default")
      (node (ref "U6") (pin "6") (pinfunction "D_6") (pintype "unspecified"))
    )
    (net (code "119") (name "unconnected-(U6-RCO-Pad15)") (class "Default")
      (node (ref "U6") (pin "15") (pinfunction "RCO_15") (pintype "unspecified"))
    )
    (net (code "120") (name "unconnected-(U7-A-Pad3)") (class "Default")
      (node (ref "U7") (pin "3") (pinfunction "A_3") (pintype "unspecified"))
    )
    (net (code "121") (name "unconnected-(U7-B-Pad4)") (class "Default")
      (node (ref "U7") (pin "4") (pinfunction "B_4") (pintype "unspecified"))
    )
    (net (code "122") (name "unconnected-(U7-C-Pad5)") (class "Default")
      (node (ref "U7") (pin "5") (pinfunction "C_5") (pintype "unspecified"))
    )
    (net (code "123") (name "unconnected-(U7-D-Pad6)") (class "Default")
      (node (ref "U7") (pin "6") (pinfunction "D_6") (pintype "unspecified"))
    )
    (net (code "124") (name "unconnected-(U7-RCO-Pad15)") (class "Default")
      (node (ref "U7") (pin "15") (pinfunction "RCO_15") (pintype "unspecified"))
    )
    (net (code "125") (name "unconnected-(U8-A-Pad3)") (class "Default")
      (node (ref "U8") (pin "3") (pinfunction "A_3") (pintype "unspecified"))
    )
    (net (code "126") (name "unconnected-(U8-B-Pad4)") (class "Default")
      (node (ref "U8") (pin "4") (pinfunction "B_4") (pintype "unspecified"))
    )
    (net (code "127") (name "unconnected-(U8-C-Pad5)") (class "Default")
      (node (ref "U8") (pin "5") (pinfunction "C_5") (pintype "unspecified"))
    )
    (net (code "128") (name "unconnected-(U8-D-Pad6)") (class "Default")
      (node (ref "U8") (pin "6") (pinfunction "D_6") (pintype "unspecified"))
    )
    (net (code "129") (name "unconnected-(U8-RCO-Pad15)") (class "Default")
      (node (ref "U8") (pin "15") (pinfunction "RCO_15") (pintype "unspecified"))
    )
    (net (code "130") (name "unconnected-(U10-4A-Pad9)") (class "Default")
      (node (ref "U10") (pin "9") (pinfunction "4A_9") (pintype "unspecified"))
    )
    (net (code "131") (name "unconnected-(U10-4Y-Pad8)") (class "Default")
      (node (ref "U10") (pin "8") (pinfunction "4Y_8") (pintype "unspecified"))
    )
    (net (code "132") (name "unconnected-(U10-5A-Pad11)") (class "Default")
      (node (ref "U10") (pin "11") (pinfunction "5A_11") (pintype "unspecified"))
    )
    (net (code "133") (name "unconnected-(U10-5Y-Pad10)") (class "Default")
      (node (ref "U10") (pin "10") (pinfunction "5Y_10") (pintype "unspecified"))
    )
    (net (code "134") (name "unconnected-(U10-6A-Pad13)") (class "Default")
      (node (ref "U10") (pin "13") (pinfunction "6A_13") (pintype "unspecified"))
    )
    (net (code "135") (name "unconnected-(U10-6Y-Pad12)") (class "Default")
      (node (ref "U10") (pin "12") (pinfunction "6Y_12") (pintype "unspecified"))
    )
    (net (code "136") (name "unconnected-(U17-3A-Pad9)") (class "Default")
      (node (ref "U17") (pin "9") (pinfunction "3A_9") (pintype "unspecified"))
    )
    (net (code "137") (name "unconnected-(U17-3B-Pad10)") (class "Default")
      (node (ref "U17") (pin "10") (pinfunction "3B_10") (pintype "unspecified"))
    )
    (net (code "138") (name "unconnected-(U17-3Y-Pad8)") (class "Default")
      (node (ref "U17") (pin "8") (pinfunction "3Y_8") (pintype "unspecified"))
    )
  )
)
